# KNLWiring.net
KiCad netlist of a schematic drawn in EAGLE
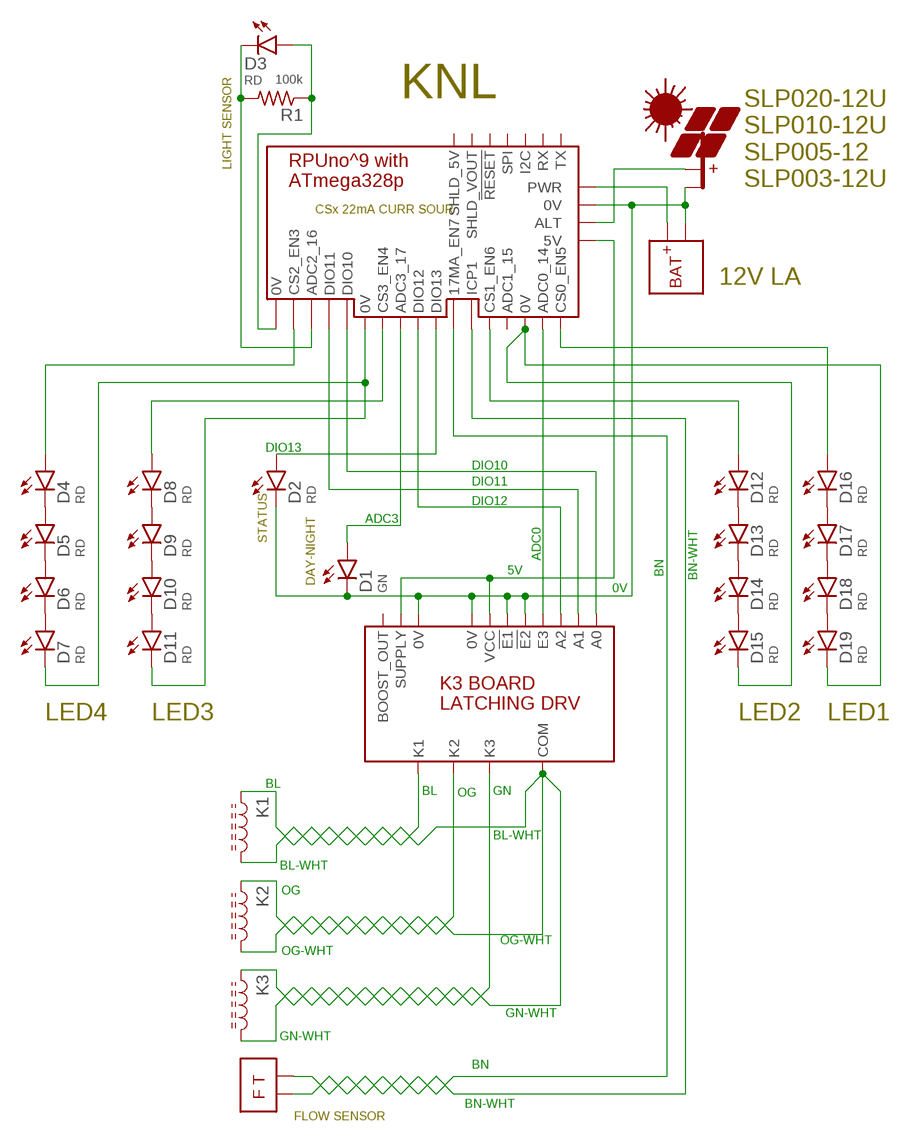
[diagram p0: schematic, sheet 1]

(export (version "E")
  (design (tool "Eeschema 10.0.6"))
  (components
    (comp (ref "BM1")
      (value "RPUNO")
      (footprint "eagle-import:NA-30")
      (libsource (lib "eagle-import") (part "RPUNO"))
    )
    (comp (ref "D1")
      (value "GN")
      (footprint "eagle-import:LED5MM")
      (libsource (lib "eagle-import") (part "LED5MM"))
    )
    (comp (ref "D2")
      (value "RD")
      (footprint "eagle-import:LED5MM")
      (libsource (lib "eagle-import") (part "LED5MM"))
    )
    (comp (ref "D3")
      (value "RD")
      (footprint "eagle-import:LED5MM")
      (libsource (lib "eagle-import") (part "LED5MM"))
    )
    (comp (ref "D4")
      (value "RD")
      (footprint "eagle-import:LED5MM")
      (libsource (lib "eagle-import") (part "LED5MM"))
    )
    (comp (ref "D5")
      (value "RD")
      (footprint "eagle-import:LED5MM")
      (libsource (lib "eagle-import") (part "LED5MM"))
    )
    (comp (ref "D6")
      (value "RD")
      (footprint "eagle-import:LED5MM")
      (libsource (lib "eagle-import") (part "LED5MM"))
    )
    (comp (ref "D7")
      (value "RD")
      (footprint "eagle-import:LED5MM")
      (libsource (lib "eagle-import") (part "LED5MM"))
    )
    (comp (ref "D8")
      (value "RD")
      (footprint "eagle-import:LED5MM")
      (libsource (lib "eagle-import") (part "LED5MM"))
    )
    (comp (ref "D9")
      (value "RD")
      (footprint "eagle-import:LED5MM")
      (libsource (lib "eagle-import") (part "LED5MM"))
    )
    (comp (ref "D10")
      (value "RD")
      (footprint "eagle-import:LED5MM")
      (libsource (lib "eagle-import") (part "LED5MM"))
    )
    (comp (ref "D11")
      (value "RD")
      (footprint "eagle-import:LED5MM")
      (libsource (lib "eagle-import") (part "LED5MM"))
    )
    (comp (ref "D12")
      (value "RD")
      (footprint "eagle-import:LED5MM")
      (libsource (lib "eagle-import") (part "LED5MM"))
    )
    (comp (ref "D13")
      (value "RD")
      (footprint "eagle-import:LED5MM")
      (libsource (lib "eagle-import") (part "LED5MM"))
    )
    (comp (ref "D14")
      (value "RD")
      (footprint "eagle-import:LED5MM")
      (libsource (lib "eagle-import") (part "LED5MM"))
    )
    (comp (ref "D15")
      (value "RD")
      (footprint "eagle-import:LED5MM")
      (libsource (lib "eagle-import") (part "LED5MM"))
    )
    (comp (ref "D16")
      (value "RD")
      (footprint "eagle-import:LED5MM")
      (libsource (lib "eagle-import") (part "LED5MM"))
    )
    (comp (ref "D17")
      (value "RD")
      (footprint "eagle-import:LED5MM")
      (libsource (lib "eagle-import") (part "LED5MM"))
    )
    (comp (ref "D18")
      (value "RD")
      (footprint "eagle-import:LED5MM")
      (libsource (lib "eagle-import") (part "LED5MM"))
    )
    (comp (ref "D19")
      (value "RD")
      (footprint "eagle-import:LED5MM")
      (libsource (lib "eagle-import") (part "LED5MM"))
    )
    (comp (ref "K1")
      (value "L0805")
      (footprint "eagle-import:C0805(2012)")
      (libsource (lib "eagle-import") (part "L0805"))
    )
    (comp (ref "K2")
      (value "L0805")
      (footprint "eagle-import:C0805(2012)")
      (libsource (lib "eagle-import") (part "L0805"))
    )
    (comp (ref "K3")
      (value "L0805")
      (footprint "eagle-import:C0805(2012)")
      (libsource (lib "eagle-import") (part "L0805"))
    )
    (comp (ref "PV4")
      (value "PV")
      (footprint "eagle-import:NA-30")
      (libsource (lib "eagle-import") (part "PV"))
    )
    (comp (ref "R1")
      (value "100k")
      (footprint "eagle-import:C0805(2012)")
      (libsource (lib "eagle-import") (part "R0805"))
    )
    (comp (ref "U$1")
      (value "K3")
      (footprint "eagle-import:NA-30")
      (libsource (lib "eagle-import") (part "K3"))
    )
    (comp (ref "U$2")
      (value "FT")
      (footprint "eagle-import:NA-30")
      (libsource (lib "eagle-import") (part "FT"))
    )
    (comp (ref "U$7")
      (value "BAT")
      (footprint "eagle-import:NA-30")
      (libsource (lib "eagle-import") (part "BAT"))
    )
  )
  (nets
    (net (code "1") (name "/0V") (class "Default")
      (node (ref "BM1") (pin "9") (pinfunction "0V_9") (pintype "bidirectional"))
      (node (ref "D1") (pin "K") (pinfunction "K_K") (pintype "passive"))
      (node (ref "D2") (pin "K") (pinfunction "K_K") (pintype "passive"))
      (node (ref "PV4") (pin "2") (pinfunction "-PV_2") (pintype "bidirectional"))
      (node (ref "U$1") (pin "1") (pinfunction "~{E1}_1") (pintype "bidirectional"))
      (node (ref "U$1") (pin "2") (pinfunction "~{E2}_2") (pintype "bidirectional"))
      (node (ref "U$1") (pin "3") (pinfunction "0V_3") (pintype "bidirectional"))
      (node (ref "U$1") (pin "4") (pinfunction "0V_4") (pintype "bidirectional"))
      (node (ref "U$7") (pin "2") (pinfunction "-BAT_2") (pintype "bidirectional"))
    )
    (net (code "2") (name "/5V") (class "Default")
      (node (ref "BM1") (pin "19") (pinfunction "5V_19") (pintype "bidirectional"))
      (node (ref "U$1") (pin "14") (pinfunction "SUPPLY_14") (pintype "bidirectional"))
      (node (ref "U$1") (pin "15") (pinfunction "VCC_15") (pintype "bidirectional"))
    )
    (net (code "3") (name "/ADC0") (class "Default")
      (node (ref "BM1") (pin "11") (pinfunction "ADC0_14_11") (pintype "bidirectional"))
      (node (ref "U$1") (pin "10") (pinfunction "E3_10") (pintype "bidirectional"))
    )
    (net (code "4") (name "/ADC3") (class "Default")
      (node (ref "BM1") (pin "16") (pinfunction "ADC3_17_16") (pintype "bidirectional"))
      (node (ref "D1") (pin "A") (pinfunction "A_A") (pintype "passive"))
    )
    (net (code "5") (name "/BL") (class "Default")
      (node (ref "K1") (pin "1") (pinfunction "1_1") (pintype "passive"))
      (node (ref "U$1") (pin "11") (pinfunction "K1_11") (pintype "bidirectional"))
    )
    (net (code "6") (name "/BL-WHT") (class "Default")
      (node (ref "K1") (pin "2") (pinfunction "2_2") (pintype "passive"))
      (node (ref "U$1") (pin "9") (pinfunction "COM_9") (pintype "bidirectional"))
    )
    (net (code "7") (name "/BN") (class "Default")
      (node (ref "BM1") (pin "21") (pinfunction "17MA_EN7_21") (pintype "bidirectional"))
      (node (ref "U$2") (pin "2") (pinfunction "PWR_2") (pintype "bidirectional"))
    )
    (net (code "8") (name "/BN-WHT") (class "Default")
      (node (ref "BM1") (pin "12") (pinfunction "ICP1_12") (pintype "bidirectional"))
      (node (ref "U$2") (pin "1") (pinfunction "PL_1") (pintype "bidirectional"))
    )
    (net (code "9") (name "/DIO10") (class "Default")
      (node (ref "BM1") (pin "15") (pinfunction "DIO10_15") (pintype "bidirectional"))
      (node (ref "U$1") (pin "5") (pinfunction "A0_5") (pintype "bidirectional"))
    )
    (net (code "10") (name "/DIO11") (class "Default")
      (node (ref "BM1") (pin "14") (pinfunction "DIO11_14") (pintype "bidirectional"))
      (node (ref "U$1") (pin "6") (pinfunction "A1_6") (pintype "bidirectional"))
    )
    (net (code "11") (name "/DIO12") (class "Default")
      (node (ref "BM1") (pin "17") (pinfunction "DIO12_17") (pintype "bidirectional"))
      (node (ref "U$1") (pin "7") (pinfunction "A2_7") (pintype "bidirectional"))
    )
    (net (code "12") (name "/DIO13") (class "Default")
      (node (ref "BM1") (pin "18") (pinfunction "DIO13_18") (pintype "bidirectional"))
      (node (ref "D2") (pin "A") (pinfunction "A_A") (pintype "passive"))
    )
    (net (code "13") (name "/GN") (class "Default")
      (node (ref "K3") (pin "1") (pinfunction "1_1") (pintype "passive"))
      (node (ref "U$1") (pin "13") (pinfunction "K3_13") (pintype "bidirectional"))
    )
    (net (code "14") (name "/GN-WHT") (class "Default")
      (node (ref "K3") (pin "2") (pinfunction "2_2") (pintype "passive"))
    )
    (net (code "15") (name "/OG") (class "Default")
      (node (ref "K2") (pin "1") (pinfunction "1_1") (pintype "passive"))
      (node (ref "U$1") (pin "12") (pinfunction "K2_12") (pintype "bidirectional"))
    )
    (net (code "16") (name "/OG-WHT") (class "Default")
      (node (ref "K2") (pin "2") (pinfunction "2_2") (pintype "passive"))
    )
    (net (code "17") (name "Net-(BM1-0V-Pad26)") (class "Default")
      (node (ref "BM1") (pin "26") (pinfunction "0V_26") (pintype "bidirectional"))
      (node (ref "D15") (pin "K") (pinfunction "K_K") (pintype "passive"))
      (node (ref "D19") (pin "K") (pinfunction "K_K") (pintype "passive"))
    )
    (net (code "18") (name "Net-(BM1-0V-Pad27)") (class "Default")
      (node (ref "BM1") (pin "27") (pinfunction "0V_27") (pintype "bidirectional"))
      (node (ref "D3") (pin "A") (pinfunction "A_A") (pintype "passive"))
      (node (ref "R1") (pin "1") (pinfunction "1_1") (pintype "passive"))
    )
    (net (code "19") (name "Net-(BM1-0V-Pad28)") (class "Default")
      (node (ref "BM1") (pin "28") (pinfunction "0V_28") (pintype "bidirectional"))
      (node (ref "D11") (pin "K") (pinfunction "K_K") (pintype "passive"))
      (node (ref "D7") (pin "K") (pinfunction "K_K") (pintype "passive"))
    )
    (net (code "20") (name "Net-(BM1-ADC2_16)") (class "Default")
      (node (ref "BM1") (pin "13") (pinfunction "ADC2_16_13") (pintype "bidirectional"))
      (node (ref "D3") (pin "K") (pinfunction "K_K") (pintype "passive"))
      (node (ref "R1") (pin "2") (pinfunction "2_2") (pintype "passive"))
    )
    (net (code "21") (name "Net-(BM1-ALT)") (class "Default")
      (node (ref "BM1") (pin "20") (pinfunction "ALT_20") (pintype "bidirectional"))
      (node (ref "PV4") (pin "1") (pinfunction "+PV_1") (pintype "bidirectional"))
    )
    (net (code "22") (name "Net-(BM1-CS0_EN5)") (class "Default")
      (node (ref "BM1") (pin "23") (pinfunction "CS0_EN5_23") (pintype "bidirectional"))
      (node (ref "D16") (pin "A") (pinfunction "A_A") (pintype "passive"))
    )
    (net (code "23") (name "Net-(BM1-CS1_EN6)") (class "Default")
      (node (ref "BM1") (pin "22") (pinfunction "CS1_EN6_22") (pintype "bidirectional"))
      (node (ref "D12") (pin "A") (pinfunction "A_A") (pintype "passive"))
    )
    (net (code "24") (name "Net-(BM1-CS2_EN3)") (class "Default")
      (node (ref "BM1") (pin "24") (pinfunction "CS2_EN3_24") (pintype "bidirectional"))
      (node (ref "D4") (pin "A") (pinfunction "A_A") (pintype "passive"))
    )
    (net (code "25") (name "Net-(BM1-CS3_EN4)") (class "Default")
      (node (ref "BM1") (pin "29") (pinfunction "CS3_EN4_29") (pintype "bidirectional"))
      (node (ref "D8") (pin "A") (pinfunction "A_A") (pintype "passive"))
    )
    (net (code "26") (name "Net-(BM1-PWR)") (class "Default")
      (node (ref "BM1") (pin "8") (pinfunction "PWR_8") (pintype "bidirectional"))
      (node (ref "U$7") (pin "1") (pinfunction "+BAT_1") (pintype "bidirectional"))
    )
    (net (code "27") (name "Net-(D4-PadK)") (class "Default")
      (node (ref "D4") (pin "K") (pinfunction "K_K") (pintype "passive"))
      (node (ref "D5") (pin "A") (pinfunction "A_A") (pintype "passive"))
    )
    (net (code "28") (name "Net-(D5-PadK)") (class "Default")
      (node (ref "D5") (pin "K") (pinfunction "K_K") (pintype "passive"))
      (node (ref "D6") (pin "A") (pinfunction "A_A") (pintype "passive"))
    )
    (net (code "29") (name "Net-(D6-PadK)") (class "Default")
      (node (ref "D6") (pin "K") (pinfunction "K_K") (pintype "passive"))
      (node (ref "D7") (pin "A") (pinfunction "A_A") (pintype "passive"))
    )
    (net (code "30") (name "Net-(D8-PadK)") (class "Default")
      (node (ref "D8") (pin "K") (pinfunction "K_K") (pintype "passive"))
      (node (ref "D9") (pin "A") (pinfunction "A_A") (pintype "passive"))
    )
    (net (code "31") (name "Net-(D10-PadA)") (class "Default")
      (node (ref "D10") (pin "A") (pinfunction "A_A") (pintype "passive"))
      (node (ref "D9") (pin "K") (pinfunction "K_K") (pintype "passive"))
    )
    (net (code "32") (name "Net-(D10-PadK)") (class "Default")
      (node (ref "D10") (pin "K") (pinfunction "K_K") (pintype "passive"))
      (node (ref "D11") (pin "A") (pinfunction "A_A") (pintype "passive"))
    )
    (net (code "33") (name "Net-(D12-PadK)") (class "Default")
      (node (ref "D12") (pin "K") (pinfunction "K_K") (pintype "passive"))
      (node (ref "D13") (pin "A") (pinfunction "A_A") (pintype "passive"))
    )
    (net (code "34") (name "Net-(D13-PadK)") (class "Default")
      (node (ref "D13") (pin "K") (pinfunction "K_K") (pintype "passive"))
      (node (ref "D14") (pin "A") (pinfunction "A_A") (pintype "passive"))
    )
    (net (code "35") (name "Net-(D14-PadK)") (class "Default")
      (node (ref "D14") (pin "K") (pinfunction "K_K") (pintype "passive"))
      (node (ref "D15") (pin "A") (pinfunction "A_A") (pintype "passive"))
    )
    (net (code "36") (name "Net-(D16-PadK)") (class "Default")
      (node (ref "D16") (pin "K") (pinfunction "K_K") (pintype "passive"))
      (node (ref "D17") (pin "A") (pinfunction "A_A") (pintype "passive"))
    )
    (net (code "37") (name "Net-(D17-PadK)") (class "Default")
      (node (ref "D17") (pin "K") (pinfunction "K_K") (pintype "passive"))
      (node (ref "D18") (pin "A") (pinfunction "A_A") (pintype "passive"))
    )
    (net (code "38") (name "Net-(D18-PadK)") (class "Default")
      (node (ref "D18") (pin "K") (pinfunction "K_K") (pintype "passive"))
      (node (ref "D19") (pin "A") (pinfunction "A_A") (pintype "passive"))
    )
    (net (code "39") (name "unconnected-(BM1-ADC1_15-Pad10)") (class "Default")
      (node (ref "BM1") (pin "10") (pinfunction "ADC1_15_10") (pintype "bidirectional"))
    )
    (net (code "40") (name "unconnected-(BM1-I2C-Pad3)") (class "Default")
      (node (ref "BM1") (pin "3") (pinfunction "I2C_3") (pintype "bidirectional"))
    )
    (net (code "41") (name "unconnected-(BM1-RX-Pad2)") (class "Default")
      (node (ref "BM1") (pin "2") (pinfunction "RX_2") (pintype "bidirectional"))
    )
    (net (code "42") (name "unconnected-(BM1-SHLD_5V-Pad6)") (class "Default")
      (node (ref "BM1") (pin "6") (pinfunction "SHLD_5V_6") (pintype "bidirectional"))
    )
    (net (code "43") (name "unconnected-(BM1-SHLD_VOUT-Pad7)") (class "Default")
      (node (ref "BM1") (pin "7") (pinfunction "SHLD_VOUT_7") (pintype "bidirectional"))
    )
    (net (code "44") (name "unconnected-(BM1-SPI-Pad4)") (class "Default")
      (node (ref "BM1") (pin "4") (pinfunction "SPI_4") (pintype "bidirectional"))
    )
    (net (code "45") (name "unconnected-(BM1-TX-Pad1)") (class "Default")
      (node (ref "BM1") (pin "1") (pinfunction "TX_1") (pintype "bidirectional"))
    )
    (net (code "46") (name "unconnected-(BM1-~{RESET}-Pad5)") (class "Default")
      (node (ref "BM1") (pin "5") (pinfunction "~{RESET}_5") (pintype "bidirectional"))
    )
    (net (code "47") (name "unconnected-(U$1-BOOST_OUT-Pad8)") (class "Default")
      (node (ref "U$1") (pin "8") (pinfunction "BOOST_OUT_8") (pintype "bidirectional"))
    )
  )
)
